# STM32F050F_Base.net
KiCad netlist of a schematic drawn in EAGLE
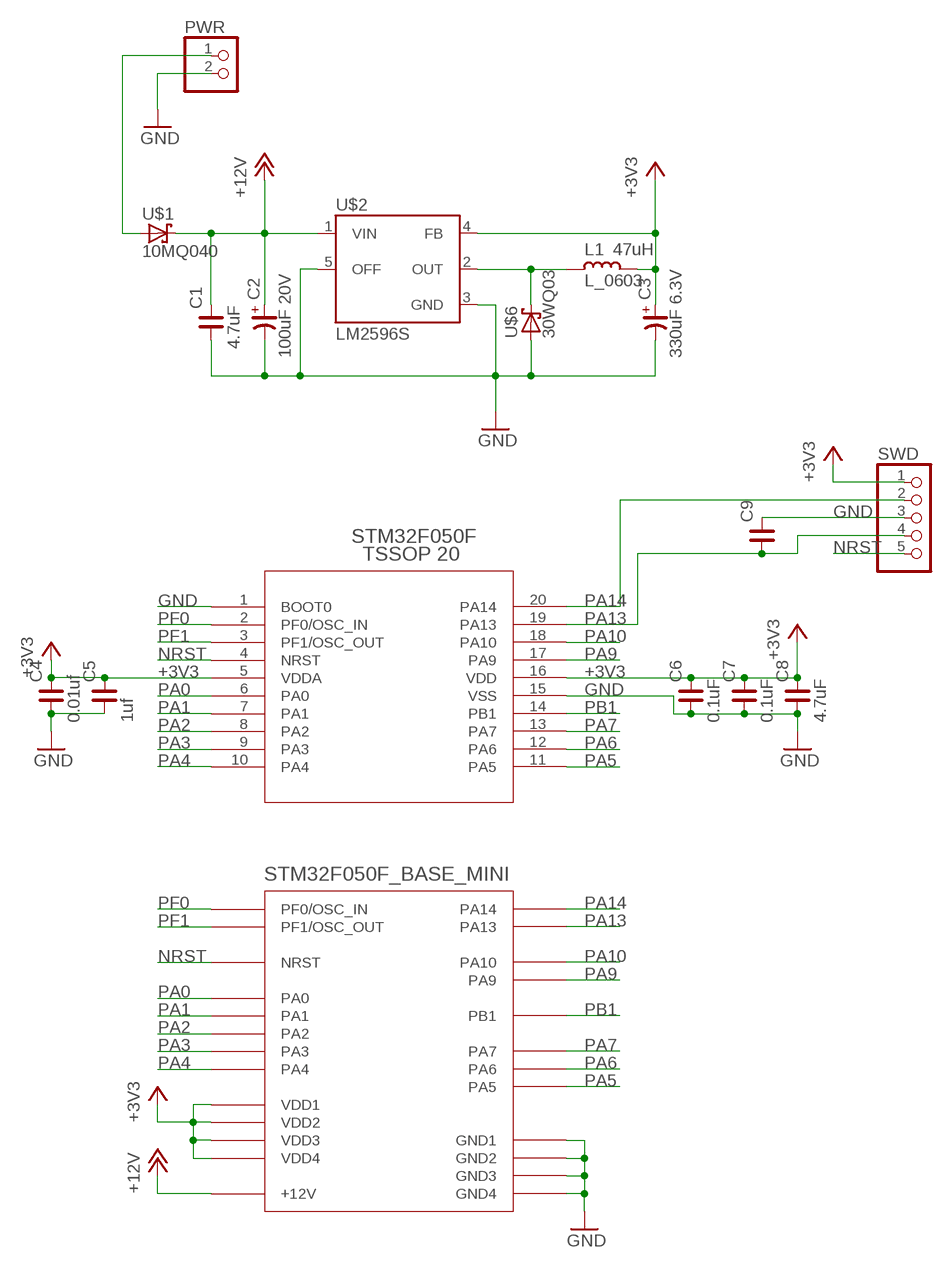
[diagram p0: schematic, sheet 1]

(export (version "E")
  (design (tool "Eeschema 10.0.6"))
  (components
    (comp (ref "C1")
      (value "4.7uF")
      (footprint "eagle-import:C1206")
      (libsource (lib "eagle-import") (part "C_1206"))
    )
    (comp (ref "C2")
      (value "100uF 20V")
      (footprint "eagle-import:C7343_T")
      (libsource (lib "eagle-import") (part "CP_7343"))
    )
    (comp (ref "C3")
      (value "330uF 6.3V")
      (footprint "eagle-import:C7343_T")
      (libsource (lib "eagle-import") (part "CP_7343"))
    )
    (comp (ref "C4")
      (value "0.01uf")
      (footprint "eagle-import:C0805")
      (libsource (lib "eagle-import") (part "C_0805"))
    )
    (comp (ref "C5")
      (value "1uf")
      (footprint "eagle-import:C0805")
      (libsource (lib "eagle-import") (part "C_0805"))
    )
    (comp (ref "C6")
      (value "0.1uF")
      (footprint "eagle-import:C0805")
      (libsource (lib "eagle-import") (part "C_0805"))
    )
    (comp (ref "C7")
      (value "0.1uF")
      (footprint "eagle-import:C0805")
      (libsource (lib "eagle-import") (part "C_0805"))
    )
    (comp (ref "C8")
      (value "4.7uF")
      (footprint "eagle-import:C1206")
      (libsource (lib "eagle-import") (part "C_1206"))
    )
    (comp (ref "C9")
      (value "C_1206")
      (footprint "eagle-import:C1206")
      (libsource (lib "eagle-import") (part "C_1206"))
    )
    (comp (ref "L1")
      (value "L_0603")
      (footprint "eagle-import:L0603")
      (fields (field (name "LCN0603T-47NJ-N") "47uH"))
      (libsource (lib "eagle-import") (part "L_0603"))
    )
    (comp (ref "PWR")
      (value "PINHD-1X02_2.54-90°-S")
      (footprint "eagle-import:1X02_90-S")
      (libsource (lib "eagle-import") (part "PINHD-1X02_2.54-90°-S"))
    )
    (comp (ref "SWD")
      (value "PINHD-1X05_2.54-90°-S")
      (footprint "eagle-import:1X05_90-S")
      (libsource (lib "eagle-import") (part "PINHD-1X05_2.54-90°-S"))
    )
    (comp (ref "U$1")
      (value "10MQ040")
      (footprint "eagle-import:SMA")
      (libsource (lib "eagle-import") (part "10MQ040"))
    )
    (comp (ref "U$2")
      (value "LM2596S")
      (footprint "eagle-import:TO263-5")
      (libsource (lib "eagle-import") (part "LM2596S"))
    )
    (comp (ref "U$3")
      (value "STM32F050F_BASE_MINI")
      (footprint "eagle-import:STM32_BASE_MINI")
      (libsource (lib "eagle-import") (part "STM32F050F_BASE_MINI"))
    )
    (comp (ref "U$4")
      (value "STM32F050F4P6")
      (footprint "eagle-import:TSSOP20")
      (libsource (lib "eagle-import") (part "STM32F050F4P6"))
    )
    (comp (ref "U$6")
      (value "30WQ03")
      (footprint "eagle-import:TO252")
      (libsource (lib "eagle-import") (part "30WQ03"))
    )
  )
  (nets
    (net (code "1") (name "+3V3") (class "Default")
      (node (ref "C3") (pin "+") (pinfunction "+_+") (pintype "passive"))
      (node (ref "C4") (pin "2") (pinfunction "2_2") (pintype "passive"))
      (node (ref "C5") (pin "2") (pinfunction "2_2") (pintype "passive"))
      (node (ref "C6") (pin "2") (pinfunction "2_2") (pintype "passive"))
      (node (ref "C7") (pin "2") (pinfunction "2_2") (pintype "passive"))
      (node (ref "C8") (pin "2") (pinfunction "2_2") (pintype "passive"))
      (node (ref "L1") (pin "1") (pinfunction "1_1") (pintype "passive"))
      (node (ref "SWD") (pin "1") (pinfunction "1_1") (pintype "passive"))
      (node (ref "U$2") (pin "4") (pinfunction "FB_4") (pintype "input"))
      (node (ref "U$3") (pin "VDD1") (pinfunction "VDD1_VDD1") (pintype "passive"))
      (node (ref "U$3") (pin "VDD2") (pinfunction "VDD2_VDD2") (pintype "passive"))
      (node (ref "U$3") (pin "VDD3") (pinfunction "VDD3_VDD3") (pintype "passive"))
      (node (ref "U$3") (pin "VDD4") (pinfunction "VDD4_VDD4") (pintype "passive"))
      (node (ref "U$4") (pin "16") (pinfunction "VDD_16") (pintype "passive"))
      (node (ref "U$4") (pin "5") (pinfunction "VDDA_5") (pintype "passive"))
    )
    (net (code "2") (name "+12V") (class "Default")
      (node (ref "C1") (pin "2") (pinfunction "2_2") (pintype "passive"))
      (node (ref "C2") (pin "+") (pinfunction "+_+") (pintype "passive"))
      (node (ref "U$1") (pin "C") (pinfunction "C_C") (pintype "passive"))
      (node (ref "U$2") (pin "1") (pinfunction "VIN_1") (pintype "power_in"))
      (node (ref "U$3") (pin "+12V") (pinfunction "+12V_+12V") (pintype "passive"))
    )
    (net (code "3") (name "/NRST") (class "Default")
      (node (ref "SWD") (pin "5") (pinfunction "5_5") (pintype "passive"))
      (node (ref "U$3") (pin "NRST") (pinfunction "NRST_NRST") (pintype "passive"))
      (node (ref "U$4") (pin "4") (pinfunction "NRST_4") (pintype "passive"))
    )
    (net (code "4") (name "/PA0") (class "Default")
      (node (ref "U$3") (pin "PA0") (pinfunction "PA0_PA0") (pintype "passive"))
      (node (ref "U$4") (pin "6") (pinfunction "PA0_6") (pintype "passive"))
    )
    (net (code "5") (name "/PA1") (class "Default")
      (node (ref "U$3") (pin "PA1") (pinfunction "PA1_PA1") (pintype "passive"))
      (node (ref "U$4") (pin "7") (pinfunction "PA1_7") (pintype "passive"))
    )
    (net (code "6") (name "/PA2") (class "Default")
      (node (ref "U$3") (pin "PA2") (pinfunction "PA2_PA2") (pintype "passive"))
      (node (ref "U$4") (pin "8") (pinfunction "PA2_8") (pintype "passive"))
    )
    (net (code "7") (name "/PA3") (class "Default")
      (node (ref "U$3") (pin "PA3") (pinfunction "PA3_PA3") (pintype "passive"))
      (node (ref "U$4") (pin "9") (pinfunction "PA3_9") (pintype "passive"))
    )
    (net (code "8") (name "/PA4") (class "Default")
      (node (ref "U$3") (pin "PA4") (pinfunction "PA4_PA4") (pintype "passive"))
      (node (ref "U$4") (pin "10") (pinfunction "PA4_10") (pintype "passive"))
    )
    (net (code "9") (name "/PA5") (class "Default")
      (node (ref "U$3") (pin "PA5") (pinfunction "PA5_PA5") (pintype "passive"))
      (node (ref "U$4") (pin "11") (pinfunction "PA5_11") (pintype "passive"))
    )
    (net (code "10") (name "/PA6") (class "Default")
      (node (ref "U$3") (pin "PA6") (pinfunction "PA6_PA6") (pintype "passive"))
      (node (ref "U$4") (pin "12") (pinfunction "PA6_12") (pintype "passive"))
    )
    (net (code "11") (name "/PA7") (class "Default")
      (node (ref "U$3") (pin "PA7") (pinfunction "PA7_PA7") (pintype "passive"))
      (node (ref "U$4") (pin "13") (pinfunction "PA7_13") (pintype "passive"))
    )
    (net (code "12") (name "/PA9") (class "Default")
      (node (ref "U$3") (pin "PA9") (pinfunction "PA9_PA9") (pintype "passive"))
      (node (ref "U$4") (pin "17") (pinfunction "PA9_17") (pintype "passive"))
    )
    (net (code "13") (name "/PA10") (class "Default")
      (node (ref "U$3") (pin "PA10") (pinfunction "PA10_PA10") (pintype "passive"))
      (node (ref "U$4") (pin "18") (pinfunction "PA10_18") (pintype "passive"))
    )
    (net (code "14") (name "/PA13") (class "Default")
      (node (ref "C9") (pin "1") (pinfunction "1_1") (pintype "passive"))
      (node (ref "SWD") (pin "4") (pinfunction "4_4") (pintype "passive"))
      (node (ref "U$3") (pin "PA13") (pinfunction "PA13_PA13") (pintype "passive"))
      (node (ref "U$4") (pin "19") (pinfunction "PA13_19") (pintype "passive"))
    )
    (net (code "15") (name "/PA14") (class "Default")
      (node (ref "SWD") (pin "2") (pinfunction "2_2") (pintype "passive"))
      (node (ref "U$3") (pin "PA14") (pinfunction "PA14_PA14") (pintype "passive"))
      (node (ref "U$4") (pin "20") (pinfunction "PA14_20") (pintype "passive"))
    )
    (net (code "16") (name "/PB1") (class "Default")
      (node (ref "U$3") (pin "PB1") (pinfunction "PB1_PB1") (pintype "passive"))
      (node (ref "U$4") (pin "14") (pinfunction "PB1_14") (pintype "passive"))
    )
    (net (code "17") (name "/PF0") (class "Default")
      (node (ref "U$3") (pin "PF0") (pinfunction "PF0/OSC_IN_PF0") (pintype "passive"))
      (node (ref "U$4") (pin "2") (pinfunction "PF0/OSC_IN_2") (pintype "passive"))
    )
    (net (code "18") (name "/PF1") (class "Default")
      (node (ref "U$3") (pin "PF1") (pinfunction "PF1/OSC_OUT_PF1") (pintype "passive"))
      (node (ref "U$4") (pin "3") (pinfunction "PF1/OSC_OUT_3") (pintype "passive"))
    )
    (net (code "19") (name "GND") (class "Default")
      (node (ref "C1") (pin "1") (pinfunction "1_1") (pintype "passive"))
      (node (ref "C2") (pin "-") (pinfunction "-_-") (pintype "passive"))
      (node (ref "C3") (pin "-") (pinfunction "-_-") (pintype "passive"))
      (node (ref "C4") (pin "1") (pinfunction "1_1") (pintype "passive"))
      (node (ref "C5") (pin "1") (pinfunction "1_1") (pintype "passive"))
      (node (ref "C6") (pin "1") (pinfunction "1_1") (pintype "passive"))
      (node (ref "C7") (pin "1") (pinfunction "1_1") (pintype "passive"))
      (node (ref "C8") (pin "1") (pinfunction "1_1") (pintype "passive"))
      (node (ref "C9") (pin "2") (pinfunction "2_2") (pintype "passive"))
      (node (ref "PWR") (pin "2") (pinfunction "2_2") (pintype "passive"))
      (node (ref "SWD") (pin "3") (pinfunction "3_3") (pintype "passive"))
      (node (ref "U$2") (pin "3") (pinfunction "GND_3") (pintype "power_in"))
      (node (ref "U$2") (pin "5") (pinfunction "OFF_5") (pintype "input"))
      (node (ref "U$3") (pin "GND1") (pinfunction "GND1_GND1") (pintype "passive"))
      (node (ref "U$3") (pin "GND2") (pinfunction "GND2_GND2") (pintype "passive"))
      (node (ref "U$3") (pin "GND3") (pinfunction "GND3_GND3") (pintype "passive"))
      (node (ref "U$3") (pin "GND4") (pinfunction "GND4_GND4") (pintype "passive"))
      (node (ref "U$4") (pin "1") (pinfunction "BOOT0_1") (pintype "passive"))
      (node (ref "U$4") (pin "15") (pinfunction "VSS_15") (pintype "passive"))
      (node (ref "U$6") (pin "1") (pinfunction "A_1") (pintype "passive"))
      (node (ref "U$6") (pin "2") (pinfunction "A_2") (pintype "passive"))
    )
    (net (code "20") (name "Net-(PWR-Pad1)") (class "Default")
      (node (ref "PWR") (pin "1") (pinfunction "1_1") (pintype "passive"))
      (node (ref "U$1") (pin "A") (pinfunction "A_A") (pintype "passive"))
    )
    (net (code "21") (name "Net-(U$2-OUT)") (class "Default")
      (node (ref "L1") (pin "2") (pinfunction "2_2") (pintype "passive"))
      (node (ref "U$2") (pin "2") (pinfunction "OUT_2") (pintype "output"))
      (node (ref "U$6") (pin "3") (pinfunction "C_3") (pintype "passive"))
    )
  )
)
